# Sheet_CL-IR-01.net
KiCad netlist of a schematic drawn in Altium Designer
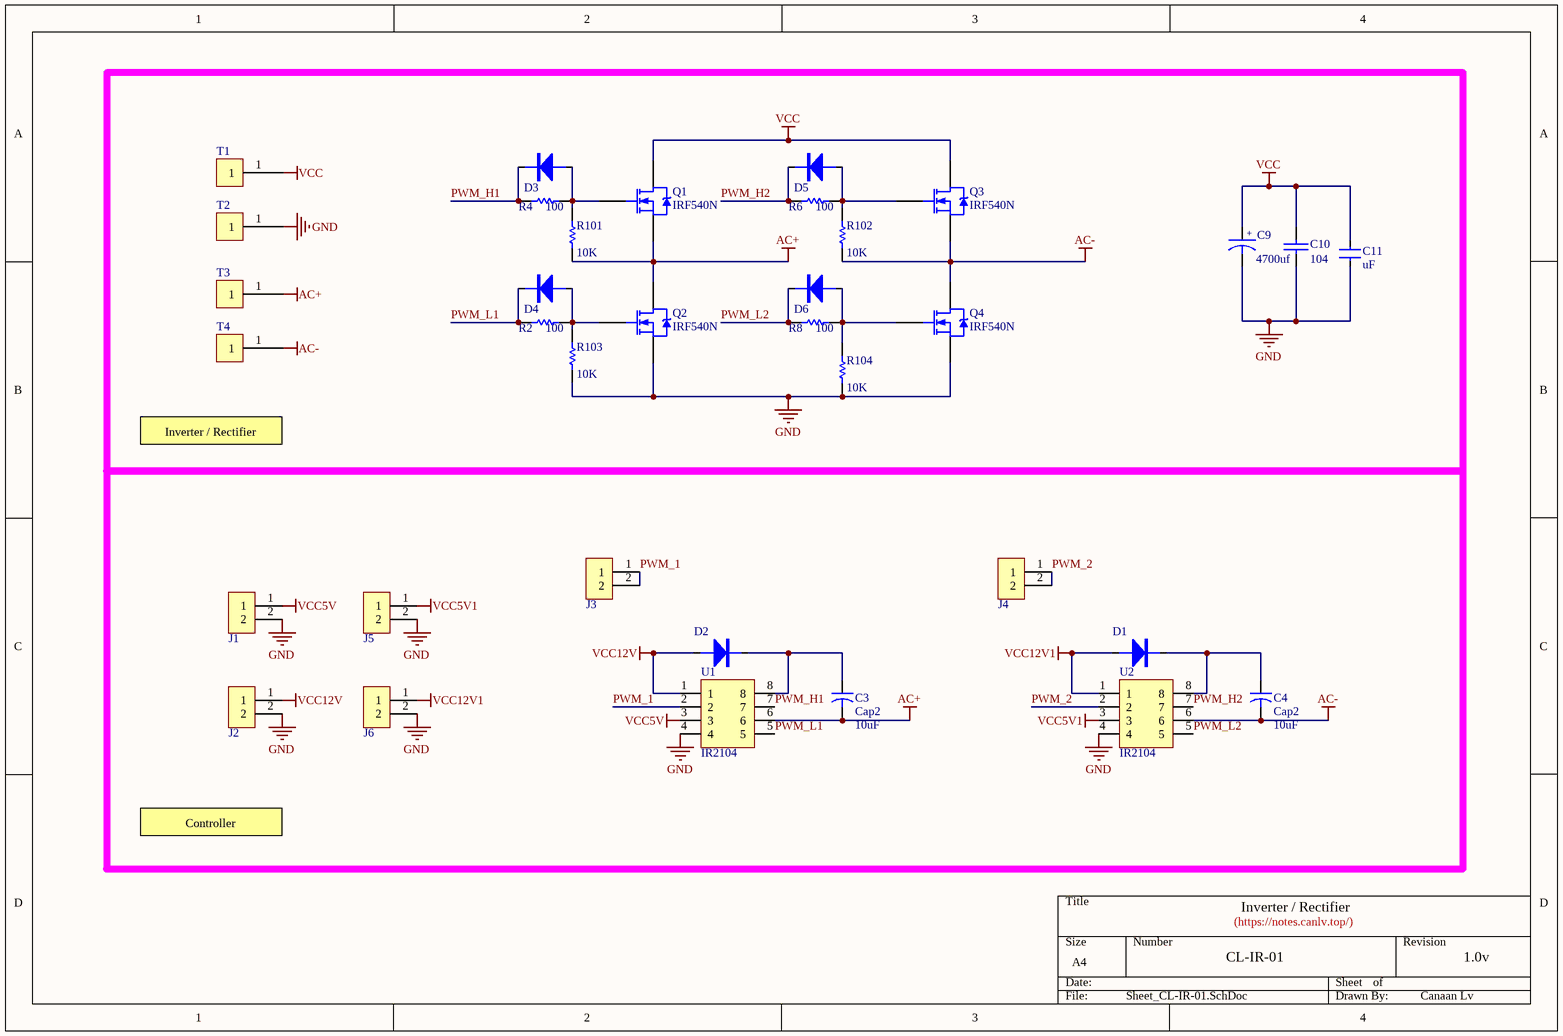
[diagram p0: Sheet_CL-IR-01.SchDoc]

(export (version "E")
  (design (tool "Eeschema 10.0.6"))
  (components
    (comp (ref "C3")
      (value "Cap2")
      (footprint "CZ0.50/25V47U")
      (description "Capacitor")
      (fields (field (name "ALTIUM_VALUE") "10uF") (field (name "PUBLISHER") "Altium Limited"))
      (libsource (lib "Miscellaneous Devices") (part "Cap2"))
    )
    (comp (ref "C4")
      (value "Cap2")
      (footprint "CZ0.50/25V47U")
      (description "Capacitor")
      (fields (field (name "ALTIUM_VALUE") "10uF") (field (name "PUBLISHER") "Altium Limited"))
      (libsource (lib "Miscellaneous Devices") (part "Cap2"))
    )
    (comp (ref "C9")
      (value "电解电容")
      (footprint "CZ16X25")
      (description "Capacitor")
      (fields (field (name "ALTIUM_UNNAMED_1") "4700uf"))
      (libsource (lib "电容") (part "电解电容"))
    )
    (comp (ref "C10")
      (value "普通电容")
      (footprint "C1206")
      (description "Capacitor")
      (fields (field (name "ALTIUM_UNNAMED_1") "104"))
      (libsource (lib "电容") (part "普通电容"))
    )
    (comp (ref "C11") (value "uF") (footprint "C0.254") (libsource (lib "电容") (part "C直插无极性")))
    (comp (ref "D1") (value "DO-41") (footprint "DO-41-2") (libsource (lib "二极管") (part "DO-41")))
    (comp (ref "D2") (value "DO-41") (footprint "DO-41-2") (libsource (lib "二极管") (part "DO-41")))
    (comp (ref "D3") (value "0805D") (footprint "0805D") (libsource (lib "二极管") (part "0805D")))
    (comp (ref "D4") (value "0805D") (footprint "0805D") (libsource (lib "二极管") (part "0805D")))
    (comp (ref "D5") (value "0805D") (footprint "0805D") (libsource (lib "二极管") (part "0805D")))
    (comp (ref "D6") (value "0805D") (footprint "0805D") (libsource (lib "二极管") (part "0805D")))
    (comp (ref "J1") (value "SIP-2") (footprint "2.54XH接插件2P") (libsource (lib "接插件") (part "SIP-2")))
    (comp (ref "J2") (value "SIP-2") (footprint "2.54XH接插件2P") (libsource (lib "接插件") (part "SIP-2")))
    (comp (ref "J3") (value "SIP-2") (footprint "2.54XH接插件2P") (libsource (lib "接插件") (part "SIP-2")))
    (comp (ref "J4") (value "SIP-2") (footprint "2.54XH接插件2P") (libsource (lib "接插件") (part "SIP-2")))
    (comp (ref "J5") (value "SIP-2") (footprint "2.54XH接插件2P") (libsource (lib "接插件") (part "SIP-2")))
    (comp (ref "J6") (value "SIP-2") (footprint "2.54XH接插件2P") (libsource (lib "接插件") (part "SIP-2")))
    (comp (ref "Q1")
      (value "IRF540N")
      (footprint "TO-220AB")
      (description "HEXFET Power MOSFET")
      (fields (field (name "PUBLISHER") "Altium Limited"))
      (libsource (lib "IR Discrete MOSFET - Power") (part "IRF540N"))
    )
    (comp (ref "Q2")
      (value "IRF540N")
      (footprint "TO-220AB")
      (description "HEXFET Power MOSFET")
      (fields (field (name "PUBLISHER") "Altium Limited"))
      (libsource (lib "IR Discrete MOSFET - Power") (part "IRF540N"))
    )
    (comp (ref "Q3")
      (value "IRF540N")
      (footprint "TO-220AB")
      (description "HEXFET Power MOSFET")
      (fields (field (name "PUBLISHER") "Altium Limited"))
      (libsource (lib "IR Discrete MOSFET - Power") (part "IRF540N"))
    )
    (comp (ref "Q4")
      (value "IRF540N")
      (footprint "TO-220AB")
      (description "HEXFET Power MOSFET")
      (fields (field (name "PUBLISHER") "Altium Limited"))
      (libsource (lib "IR Discrete MOSFET - Power") (part "IRF540N"))
    )
    (comp (ref "R2")
      (value "100")
      (footprint "R1206")
      (description "Resistor")
      (fields (field (name "PUBLISHER") "Altium Limited"))
      (libsource (lib "Miscellaneous Devices") (part "Res1"))
    )
    (comp (ref "R4")
      (value "100")
      (footprint "R1206")
      (description "Resistor")
      (fields (field (name "PUBLISHER") "Altium Limited"))
      (libsource (lib "Miscellaneous Devices") (part "Res1"))
    )
    (comp (ref "R6")
      (value "100")
      (footprint "R1206")
      (description "Resistor")
      (fields (field (name "PUBLISHER") "Altium Limited"))
      (libsource (lib "Miscellaneous Devices") (part "Res1"))
    )
    (comp (ref "R8")
      (value "100")
      (footprint "R1206")
      (description "Resistor")
      (fields (field (name "PUBLISHER") "Altium Limited"))
      (libsource (lib "Miscellaneous Devices") (part "Res1"))
    )
    (comp (ref "R101")
      (value "10K")
      (footprint "R1206")
      (description "Resistor")
      (fields (field (name "PUBLISHER") "Altium Limited"))
      (libsource (lib "Miscellaneous Devices") (part "Res1"))
    )
    (comp (ref "R102")
      (value "10K")
      (footprint "R1206")
      (description "Resistor")
      (fields (field (name "PUBLISHER") "Altium Limited"))
      (libsource (lib "Miscellaneous Devices") (part "Res1"))
    )
    (comp (ref "R103")
      (value "10K")
      (footprint "R1206")
      (description "Resistor")
      (fields (field (name "PUBLISHER") "Altium Limited"))
      (libsource (lib "Miscellaneous Devices") (part "Res1"))
    )
    (comp (ref "R104")
      (value "10K")
      (footprint "R1206")
      (description "Resistor")
      (fields (field (name "PUBLISHER") "Altium Limited"))
      (libsource (lib "Miscellaneous Devices") (part "Res1"))
    )
    (comp (ref "T1") (value "~") (footprint "香蕉接线柱Red_6mm") (libsource (lib "Schlib1") (part "TEST_I")))
    (comp (ref "T2") (value "~") (footprint "香蕉接线柱Red_6mm") (libsource (lib "Schlib1") (part "TEST_I")))
    (comp (ref "T3") (value "~") (footprint "香蕉接线柱Red_6mm") (libsource (lib "Schlib1") (part "TEST_I")))
    (comp (ref "T4") (value "~") (footprint "香蕉接线柱Red_6mm") (libsource (lib "Schlib1") (part "TEST_I")))
    (comp (ref "U1") (value "IR2104") (footprint "SOP8") (libsource (lib "Schlib1") (part "Component_1")))
    (comp (ref "U2") (value "IR2104") (footprint "SOP8") (libsource (lib "Schlib1") (part "Component_1")))
  )
  (nets
    (net (code "1") (name "/PWM_1") (class "Default")
      (node (ref "J3") (pin "1") (pinfunction "1_1") (pintype "passive"))
      (node (ref "J3") (pin "2") (pinfunction "2_2") (pintype "passive"))
      (node (ref "U1") (pin "2") (pinfunction "2_2") (pintype "passive"))
    )
    (net (code "2") (name "/PWM_2") (class "Default")
      (node (ref "J4") (pin "1") (pinfunction "1_1") (pintype "passive"))
      (node (ref "J4") (pin "2") (pinfunction "2_2") (pintype "passive"))
      (node (ref "U2") (pin "2") (pinfunction "2_2") (pintype "passive"))
    )
    (net (code "3") (name "/PWM_H1") (class "Default")
      (node (ref "D3") (pin "K") (pinfunction "2_K") (pintype "passive"))
      (node (ref "R4") (pin "1") (pinfunction "1_1") (pintype "passive"))
      (node (ref "U1") (pin "7") (pinfunction "7_7") (pintype "passive"))
    )
    (net (code "4") (name "/PWM_H2") (class "Default")
      (node (ref "D5") (pin "K") (pinfunction "2_K") (pintype "passive"))
      (node (ref "R6") (pin "1") (pinfunction "1_1") (pintype "passive"))
      (node (ref "U2") (pin "7") (pinfunction "7_7") (pintype "passive"))
    )
    (net (code "5") (name "/PWM_L1") (class "Default")
      (node (ref "D4") (pin "K") (pinfunction "2_K") (pintype "passive"))
      (node (ref "R2") (pin "1") (pinfunction "1_1") (pintype "passive"))
      (node (ref "U1") (pin "5") (pinfunction "5_5") (pintype "passive"))
    )
    (net (code "6") (name "/PWM_L2") (class "Default")
      (node (ref "D6") (pin "K") (pinfunction "2_K") (pintype "passive"))
      (node (ref "R8") (pin "1") (pinfunction "1_1") (pintype "passive"))
      (node (ref "U2") (pin "5") (pinfunction "5_5") (pintype "passive"))
    )
    (net (code "7") (name "AC+") (class "Default")
      (node (ref "C3") (pin "2") (pinfunction "2_2") (pintype "passive"))
      (node (ref "Q1") (pin "3") (pinfunction "S_3") (pintype "passive"))
      (node (ref "Q2") (pin "2") (pinfunction "D_2") (pintype "passive"))
      (node (ref "R101") (pin "1") (pinfunction "1_1") (pintype "passive"))
      (node (ref "T3") (pin "1") (pinfunction "1_1") (pintype "passive"))
      (node (ref "U1") (pin "6") (pinfunction "6_6") (pintype "passive"))
    )
    (net (code "8") (name "AC-") (class "Default")
      (node (ref "C4") (pin "2") (pinfunction "2_2") (pintype "passive"))
      (node (ref "Q3") (pin "3") (pinfunction "S_3") (pintype "passive"))
      (node (ref "Q4") (pin "2") (pinfunction "D_2") (pintype "passive"))
      (node (ref "R102") (pin "1") (pinfunction "1_1") (pintype "passive"))
      (node (ref "T4") (pin "1") (pinfunction "1_1") (pintype "passive"))
      (node (ref "U2") (pin "6") (pinfunction "6_6") (pintype "passive"))
    )
    (net (code "9") (name "GND") (class "Default")
      (node (ref "C10") (pin "2") (pinfunction "2_2") (pintype "passive"))
      (node (ref "C11") (pin "2") (pinfunction "2_2") (pintype "passive"))
      (node (ref "C9") (pin "2") (pinfunction "2_2") (pintype "passive"))
      (node (ref "J1") (pin "2") (pinfunction "2_2") (pintype "passive"))
      (node (ref "J2") (pin "2") (pinfunction "2_2") (pintype "passive"))
      (node (ref "J5") (pin "2") (pinfunction "2_2") (pintype "passive"))
      (node (ref "J6") (pin "2") (pinfunction "2_2") (pintype "passive"))
      (node (ref "Q2") (pin "3") (pinfunction "S_3") (pintype "passive"))
      (node (ref "Q4") (pin "3") (pinfunction "S_3") (pintype "passive"))
      (node (ref "R103") (pin "2") (pinfunction "2_2") (pintype "passive"))
      (node (ref "R104") (pin "2") (pinfunction "2_2") (pintype "passive"))
      (node (ref "T2") (pin "1") (pinfunction "1_1") (pintype "passive"))
      (node (ref "U1") (pin "4") (pinfunction "4_4") (pintype "passive"))
      (node (ref "U2") (pin "4") (pinfunction "4_4") (pintype "passive"))
    )
    (net (code "10") (name "Net-(D1-2)") (class "Default")
      (node (ref "C4") (pin "1") (pinfunction "1_1") (pintype "passive"))
      (node (ref "D1") (pin "K") (pinfunction "2_K") (pintype "passive"))
      (node (ref "U2") (pin "8") (pinfunction "8_8") (pintype "passive"))
    )
    (net (code "11") (name "Net-(D2-2)") (class "Default")
      (node (ref "C3") (pin "1") (pinfunction "1_1") (pintype "passive"))
      (node (ref "D2") (pin "K") (pinfunction "2_K") (pintype "passive"))
      (node (ref "U1") (pin "8") (pinfunction "8_8") (pintype "passive"))
    )
    (net (code "12") (name "Net-(D3-1)") (class "Default")
      (node (ref "D3") (pin "A") (pinfunction "1_A") (pintype "passive"))
      (node (ref "Q1") (pin "1") (pinfunction "G_1") (pintype "passive"))
      (node (ref "R101") (pin "2") (pinfunction "2_2") (pintype "passive"))
      (node (ref "R4") (pin "2") (pinfunction "2_2") (pintype "passive"))
    )
    (net (code "13") (name "Net-(D4-1)") (class "Default")
      (node (ref "D4") (pin "A") (pinfunction "1_A") (pintype "passive"))
      (node (ref "Q2") (pin "1") (pinfunction "G_1") (pintype "passive"))
      (node (ref "R103") (pin "1") (pinfunction "1_1") (pintype "passive"))
      (node (ref "R2") (pin "2") (pinfunction "2_2") (pintype "passive"))
    )
    (net (code "14") (name "Net-(D5-1)") (class "Default")
      (node (ref "D5") (pin "A") (pinfunction "1_A") (pintype "passive"))
      (node (ref "Q3") (pin "1") (pinfunction "G_1") (pintype "passive"))
      (node (ref "R102") (pin "2") (pinfunction "2_2") (pintype "passive"))
      (node (ref "R6") (pin "2") (pinfunction "2_2") (pintype "passive"))
    )
    (net (code "15") (name "Net-(D6-1)") (class "Default")
      (node (ref "D6") (pin "A") (pinfunction "1_A") (pintype "passive"))
      (node (ref "Q4") (pin "1") (pinfunction "G_1") (pintype "passive"))
      (node (ref "R104") (pin "1") (pinfunction "1_1") (pintype "passive"))
      (node (ref "R8") (pin "2") (pinfunction "2_2") (pintype "passive"))
    )
    (net (code "16") (name "VCC") (class "Default")
      (node (ref "C10") (pin "1") (pinfunction "1_1") (pintype "passive"))
      (node (ref "C11") (pin "1") (pinfunction "1_1") (pintype "passive"))
      (node (ref "C9") (pin "1") (pinfunction "1_1") (pintype "passive"))
      (node (ref "Q1") (pin "2") (pinfunction "D_2") (pintype "passive"))
      (node (ref "Q3") (pin "2") (pinfunction "D_2") (pintype "passive"))
      (node (ref "T1") (pin "1") (pinfunction "1_1") (pintype "passive"))
    )
    (net (code "17") (name "VCC5V") (class "Default")
      (node (ref "J1") (pin "1") (pinfunction "1_1") (pintype "passive"))
      (node (ref "U1") (pin "3") (pinfunction "3_3") (pintype "passive"))
    )
    (net (code "18") (name "VCC5V1") (class "Default")
      (node (ref "J5") (pin "1") (pinfunction "1_1") (pintype "passive"))
      (node (ref "U2") (pin "3") (pinfunction "3_3") (pintype "passive"))
    )
    (net (code "19") (name "VCC12V") (class "Default")
      (node (ref "D2") (pin "A") (pinfunction "1_A") (pintype "passive"))
      (node (ref "J2") (pin "1") (pinfunction "1_1") (pintype "passive"))
      (node (ref "U1") (pin "1") (pinfunction "1_1") (pintype "passive"))
    )
    (net (code "20") (name "VCC12V1") (class "Default")
      (node (ref "D1") (pin "A") (pinfunction "1_A") (pintype "passive"))
      (node (ref "J6") (pin "1") (pinfunction "1_1") (pintype "passive"))
      (node (ref "U2") (pin "1") (pinfunction "1_1") (pintype "passive"))
    )
  )
)
